# microBackpack.net
KiCad netlist of a schematic drawn in EAGLE
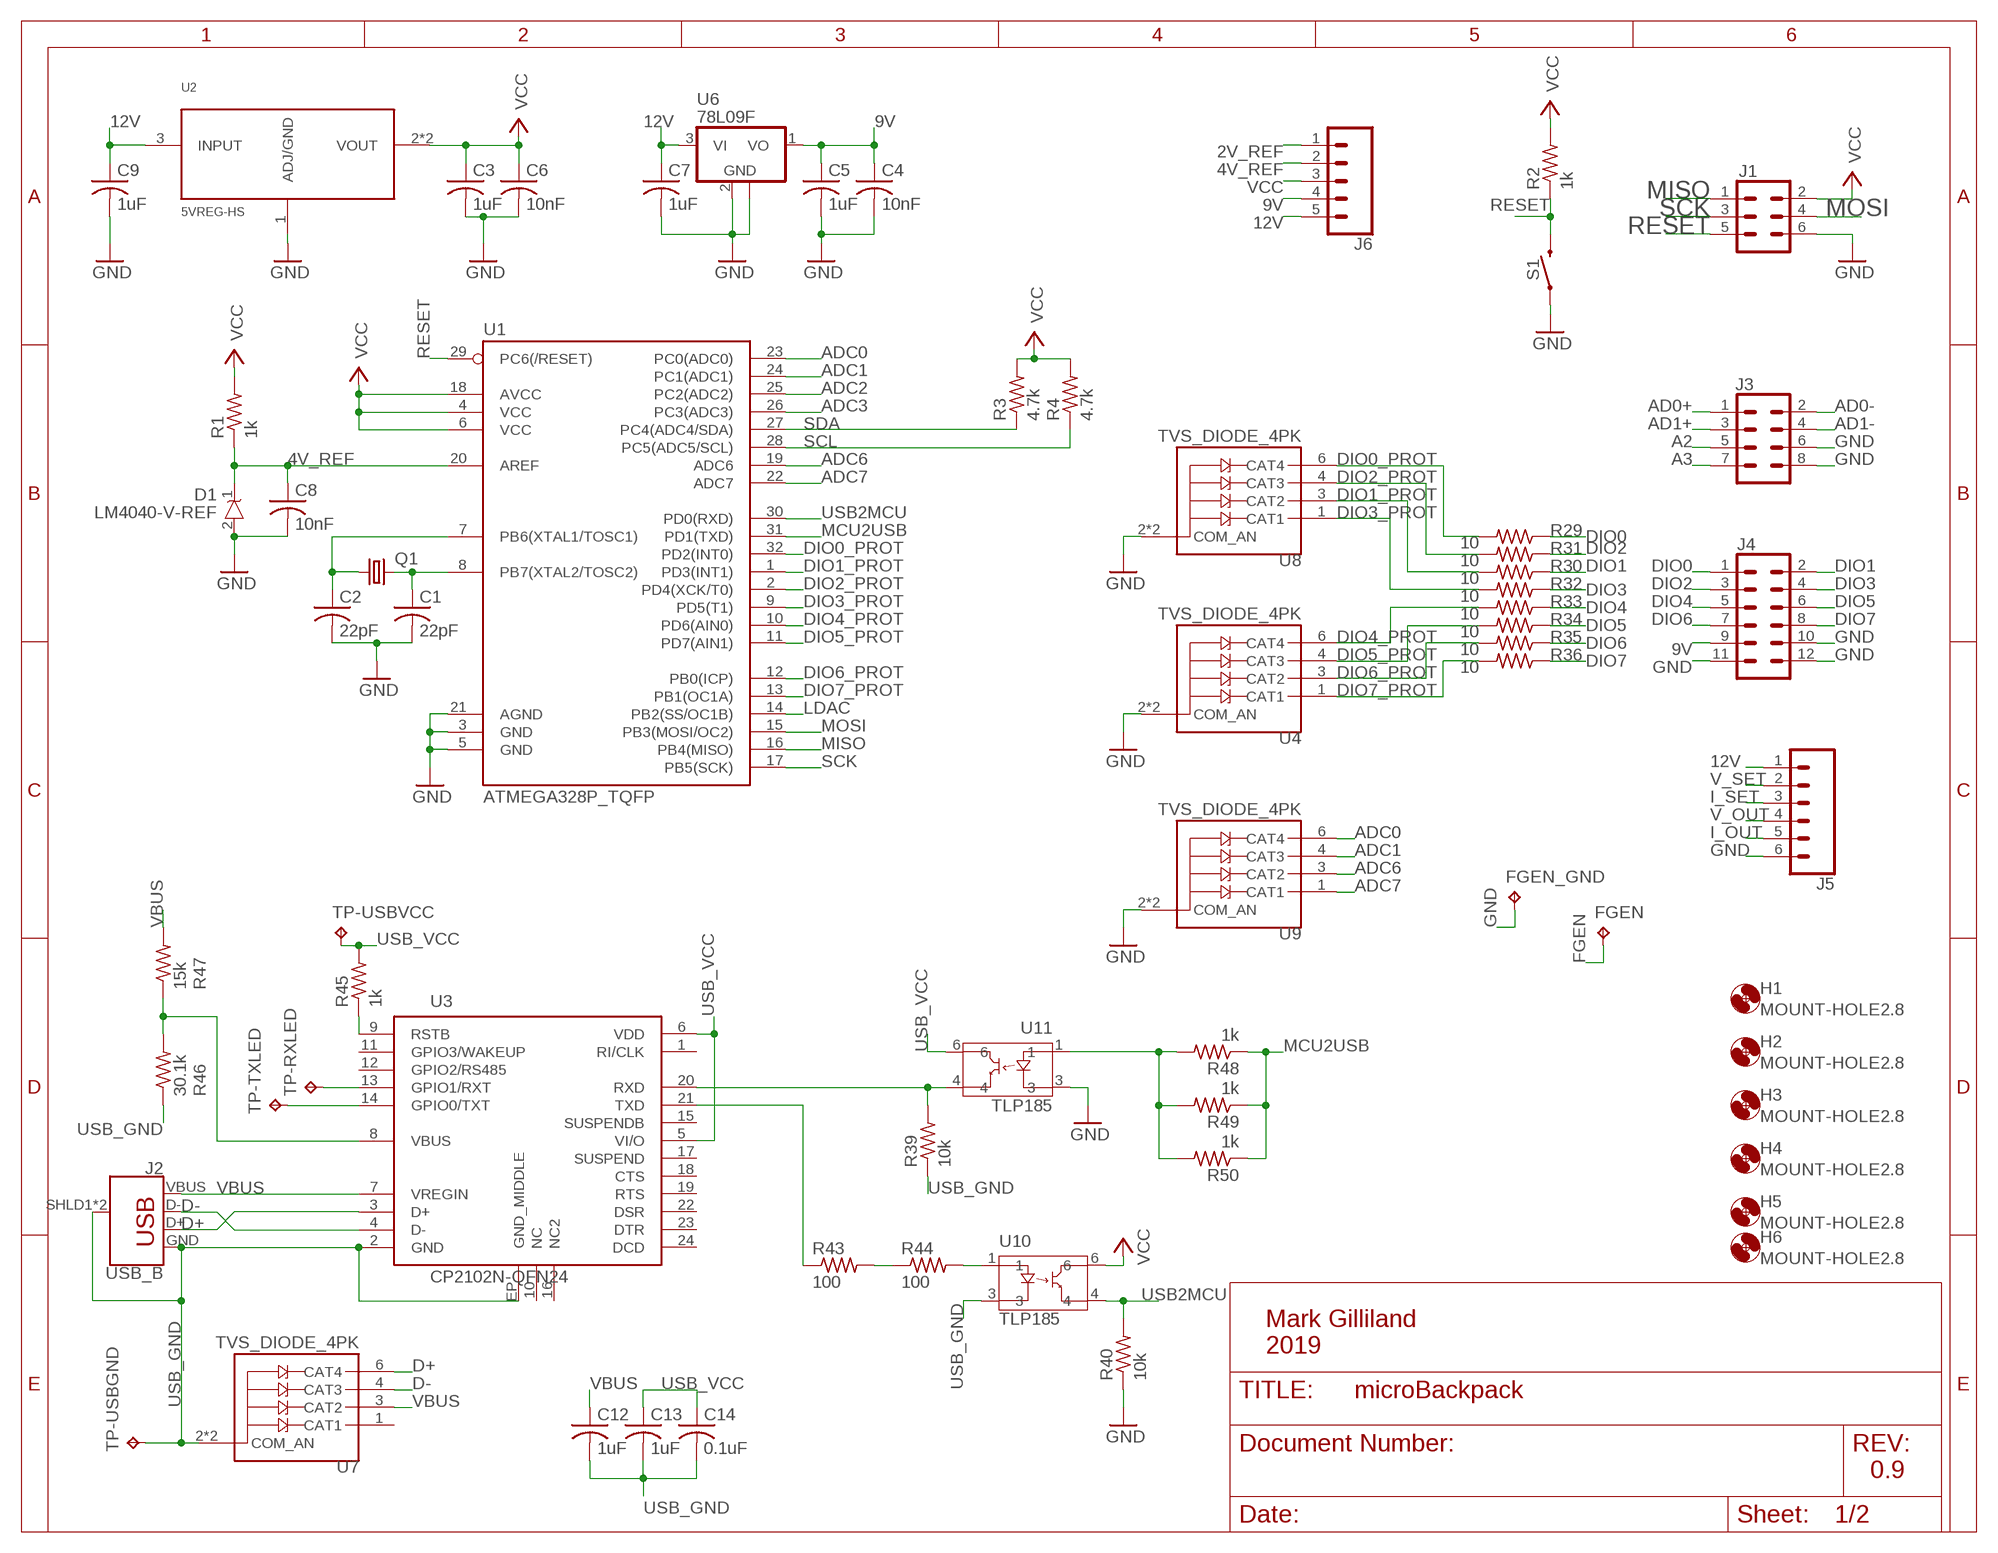
[diagram p0: schematic, sheet 1]
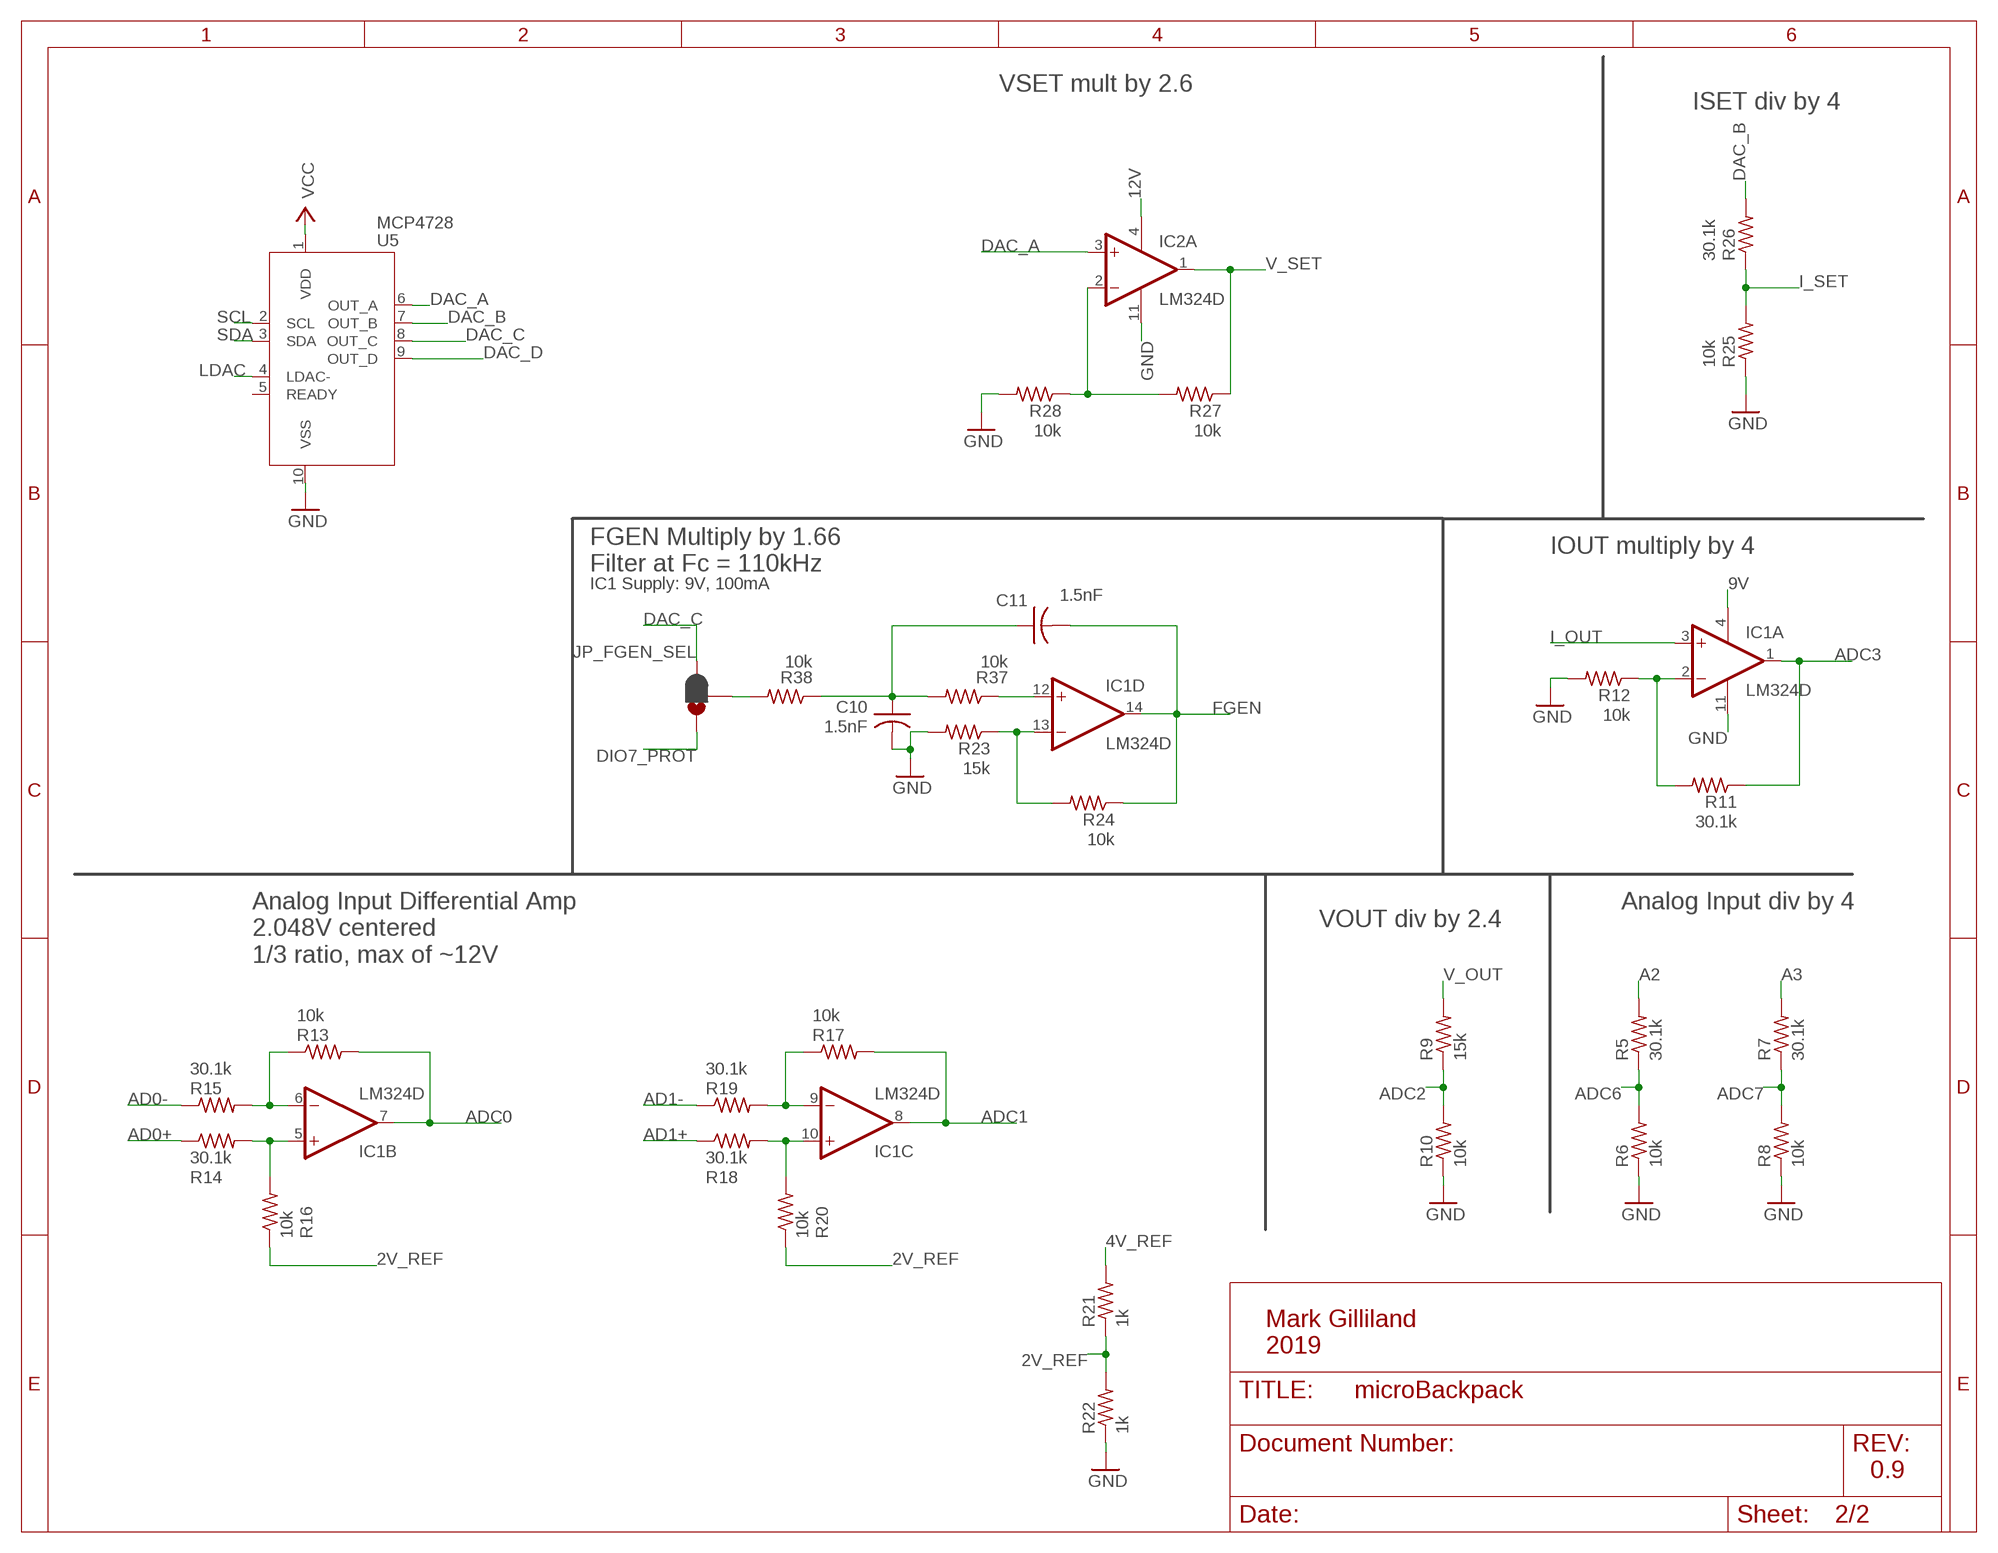
[diagram p1: schematic, sheet 2]

(export (version "E")
  (design (tool "Eeschema 10.0.6"))
  (components
    (comp (ref "C10")
      (value "1.5nF")
      (footprint "eagle-import:C0805")
      (libsource (lib "eagle-import") (part "C-USC0805"))
    )
    (comp (ref "C11")
      (value "1.5nF")
      (footprint "eagle-import:C0805")
      (libsource (lib "eagle-import") (part "C-USC0805"))
    )
    (comp (ref "IC1")
      (value "LM324D")
      (footprint "eagle-import:SO14")
      (libsource (lib "eagle-import") (part "LM324D"))
    )
    (comp (ref "IC2")
      (value "LM324D")
      (footprint "eagle-import:SO14")
      (libsource (lib "eagle-import") (part "LM324D"))
    )
    (comp (ref "JP_FGEN_SEL")
      (value "JUMPER-SMT_3_1-NC_PASTE_SILK")
      (footprint "eagle-import:SMT-JUMPER_3_1-NC_PASTE_SILK")
      (libsource (lib "eagle-import") (part "JUMPER-SMT_3_1-NC_PASTE_SILK"))
    )
    (comp (ref "R5")
      (value "30.1k")
      (footprint "eagle-import:R0805")
      (libsource (lib "eagle-import") (part "R-US_R0805"))
    )
    (comp (ref "R6")
      (value "10k")
      (footprint "eagle-import:R0805")
      (libsource (lib "eagle-import") (part "R-US_R0805"))
    )
    (comp (ref "R7")
      (value "30.1k")
      (footprint "eagle-import:R0805")
      (libsource (lib "eagle-import") (part "R-US_R0805"))
    )
    (comp (ref "R8")
      (value "10k")
      (footprint "eagle-import:R0805")
      (libsource (lib "eagle-import") (part "R-US_R0805"))
    )
    (comp (ref "R9")
      (value "15k")
      (footprint "eagle-import:R0805")
      (libsource (lib "eagle-import") (part "R-US_R0805"))
    )
    (comp (ref "R10")
      (value "10k")
      (footprint "eagle-import:R0805")
      (libsource (lib "eagle-import") (part "R-US_R0805"))
    )
    (comp (ref "R11")
      (value "30.1k")
      (footprint "eagle-import:R0805")
      (libsource (lib "eagle-import") (part "R-US_R0805"))
    )
    (comp (ref "R12")
      (value "10k")
      (footprint "eagle-import:R0805")
      (libsource (lib "eagle-import") (part "R-US_R0805"))
    )
    (comp (ref "R13")
      (value "10k")
      (footprint "eagle-import:R0805")
      (libsource (lib "eagle-import") (part "R-US_R0805"))
    )
    (comp (ref "R14")
      (value "30.1k")
      (footprint "eagle-import:R0805")
      (libsource (lib "eagle-import") (part "R-US_R0805"))
    )
    (comp (ref "R15")
      (value "30.1k")
      (footprint "eagle-import:R0805")
      (libsource (lib "eagle-import") (part "R-US_R0805"))
    )
    (comp (ref "R16")
      (value "10k")
      (footprint "eagle-import:R0805")
      (libsource (lib "eagle-import") (part "R-US_R0805"))
    )
    (comp (ref "R17")
      (value "10k")
      (footprint "eagle-import:R0805")
      (libsource (lib "eagle-import") (part "R-US_R0805"))
    )
    (comp (ref "R18")
      (value "30.1k")
      (footprint "eagle-import:R0805")
      (libsource (lib "eagle-import") (part "R-US_R0805"))
    )
    (comp (ref "R19")
      (value "30.1k")
      (footprint "eagle-import:R0805")
      (libsource (lib "eagle-import") (part "R-US_R0805"))
    )
    (comp (ref "R20")
      (value "10k")
      (footprint "eagle-import:R0805")
      (libsource (lib "eagle-import") (part "R-US_R0805"))
    )
    (comp (ref "R21")
      (value "1k")
      (footprint "eagle-import:R0805")
      (libsource (lib "eagle-import") (part "R-US_R0805"))
    )
    (comp (ref "R22")
      (value "1k")
      (footprint "eagle-import:R0805")
      (libsource (lib "eagle-import") (part "R-US_R0805"))
    )
    (comp (ref "R23")
      (value "15k")
      (footprint "eagle-import:R0805")
      (libsource (lib "eagle-import") (part "R-US_R0805"))
    )
    (comp (ref "R24")
      (value "10k")
      (footprint "eagle-import:R0805")
      (libsource (lib "eagle-import") (part "R-US_R0805"))
    )
    (comp (ref "R25")
      (value "10k")
      (footprint "eagle-import:R0805")
      (libsource (lib "eagle-import") (part "R-US_R0805"))
    )
    (comp (ref "R26")
      (value "30.1k")
      (footprint "eagle-import:R0805")
      (libsource (lib "eagle-import") (part "R-US_R0805"))
    )
    (comp (ref "R27")
      (value "10k")
      (footprint "eagle-import:R0805")
      (libsource (lib "eagle-import") (part "R-US_R0805"))
    )
    (comp (ref "R28")
      (value "10k")
      (footprint "eagle-import:R0805")
      (libsource (lib "eagle-import") (part "R-US_R0805"))
    )
    (comp (ref "R37")
      (value "10k")
      (footprint "eagle-import:R0805")
      (libsource (lib "eagle-import") (part "R-US_R0805"))
    )
    (comp (ref "R38")
      (value "10k")
      (footprint "eagle-import:R0805")
      (libsource (lib "eagle-import") (part "R-US_R0805"))
    )
    (comp (ref "U5")
      (value "MCP4728")
      (footprint "eagle-import:MSOP10")
      (libsource (lib "eagle-import") (part "MCP4728"))
    )
    (comp (ref "C1")
      (value "22pF")
      (footprint "eagle-import:C0805")
      (libsource (lib "eagle-import") (part "C-USC0805"))
    )
    (comp (ref "C2")
      (value "22pF")
      (footprint "eagle-import:C0805")
      (libsource (lib "eagle-import") (part "C-USC0805"))
    )
    (comp (ref "C3")
      (value "1uF")
      (footprint "eagle-import:C0805")
      (libsource (lib "eagle-import") (part "C-USC0805"))
    )
    (comp (ref "C4")
      (value "10nF")
      (footprint "eagle-import:C0805")
      (libsource (lib "eagle-import") (part "C-USC0805"))
    )
    (comp (ref "C5")
      (value "1uF")
      (footprint "eagle-import:C0805")
      (libsource (lib "eagle-import") (part "C-USC0805"))
    )
    (comp (ref "C6")
      (value "10nF")
      (footprint "eagle-import:C0805")
      (libsource (lib "eagle-import") (part "C-USC0805"))
    )
    (comp (ref "C7")
      (value "1uF")
      (footprint "eagle-import:C0805")
      (libsource (lib "eagle-import") (part "C-USC0805"))
    )
    (comp (ref "C8")
      (value "10nF")
      (footprint "eagle-import:C0805")
      (libsource (lib "eagle-import") (part "C-USC0805"))
    )
    (comp (ref "C9")
      (value "1uF")
      (footprint "eagle-import:C0805")
      (libsource (lib "eagle-import") (part "C-USC0805"))
    )
    (comp (ref "C12")
      (value "1uF")
      (footprint "eagle-import:C0805")
      (libsource (lib "eagle-import") (part "C-USC0805"))
    )
    (comp (ref "C13")
      (value "1uF")
      (footprint "eagle-import:C0805")
      (libsource (lib "eagle-import") (part "C-USC0805"))
    )
    (comp (ref "C14")
      (value "0.1uF")
      (footprint "eagle-import:C0805")
      (libsource (lib "eagle-import") (part "C-USC0805"))
    )
    (comp (ref "D1")
      (value "LM4040-V-REF")
      (footprint "eagle-import:SOT23")
      (libsource (lib "eagle-import") (part "LM4040-V-REF"))
    )
    (comp (ref "FGEN")
      (value "TPPAD1-20Y")
      (footprint "eagle-import:P1-20Y")
      (libsource (lib "eagle-import") (part "TPPAD1-20Y"))
    )
    (comp (ref "FGEN_GND")
      (value "TPPAD1-20Y")
      (footprint "eagle-import:P1-20Y")
      (libsource (lib "eagle-import") (part "TPPAD1-20Y"))
    )
    (comp (ref "H1")
      (value "MOUNT-HOLE2.8")
      (footprint "eagle-import:2,8")
      (libsource (lib "eagle-import") (part "MOUNT-HOLE2.8"))
    )
    (comp (ref "H2")
      (value "MOUNT-HOLE2.8")
      (footprint "eagle-import:2,8")
      (libsource (lib "eagle-import") (part "MOUNT-HOLE2.8"))
    )
    (comp (ref "H3")
      (value "MOUNT-HOLE2.8")
      (footprint "eagle-import:2,8")
      (libsource (lib "eagle-import") (part "MOUNT-HOLE2.8"))
    )
    (comp (ref "H4")
      (value "MOUNT-HOLE2.8")
      (footprint "eagle-import:2,8")
      (libsource (lib "eagle-import") (part "MOUNT-HOLE2.8"))
    )
    (comp (ref "H5")
      (value "MOUNT-HOLE2.8")
      (footprint "eagle-import:2,8")
      (libsource (lib "eagle-import") (part "MOUNT-HOLE2.8"))
    )
    (comp (ref "H6")
      (value "MOUNT-HOLE2.8")
      (footprint "eagle-import:2,8")
      (libsource (lib "eagle-import") (part "MOUNT-HOLE2.8"))
    )
    (comp (ref "J1")
      (value "CONN_03X22X3_SILK_MALE_PTH")
      (footprint "eagle-import:2X3")
      (libsource (lib "eagle-import") (part "CONN_03X22X3_SILK_MALE_PTH"))
    )
    (comp (ref "J2")
      (value "USB_B")
      (footprint "eagle-import:USB-B-PTH-VERT")
      (libsource (lib "eagle-import") (part "USB_B"))
    )
    (comp (ref "J3")
      (value "CONN_04X2")
      (footprint "eagle-import:2X4")
      (libsource (lib "eagle-import") (part "CONN_04X2"))
    )
    (comp (ref "J4")
      (value "2X6 FEMALE")
      (footprint "eagle-import:2X6")
      (libsource (lib "eagle-import") (part "CONN_06X2PTH_FEMALE"))
    )
    (comp (ref "J5")
      (value "CONN_06SILK_FEMALE_PTH")
      (footprint "eagle-import:1X06")
      (libsource (lib "eagle-import") (part "CONN_06SILK_FEMALE_PTH"))
    )
    (comp (ref "J6")
      (value "CONN_05NO_SILK")
      (footprint "eagle-import:1X05_NO_SILK")
      (libsource (lib "eagle-import") (part "CONN_05NO_SILK"))
    )
    (comp (ref "Q1")
      (value "CRYSTALHC49U70")
      (footprint "eagle-import:HC49U70")
      (libsource (lib "eagle-import") (part "CRYSTALHC49U70"))
    )
    (comp (ref "R1")
      (value "1k")
      (footprint "eagle-import:R0805")
      (libsource (lib "eagle-import") (part "R-US_R0805"))
    )
    (comp (ref "R2")
      (value "1k")
      (footprint "eagle-import:R0805")
      (libsource (lib "eagle-import") (part "R-US_R0805"))
    )
    (comp (ref "R3")
      (value "4.7k")
      (footprint "eagle-import:R0805")
      (libsource (lib "eagle-import") (part "R-US_R0805"))
    )
    (comp (ref "R4")
      (value "4.7k")
      (footprint "eagle-import:R0805")
      (libsource (lib "eagle-import") (part "R-US_R0805"))
    )
    (comp (ref "R29")
      (value "10")
      (footprint "eagle-import:R0805")
      (libsource (lib "eagle-import") (part "R-US_R0805"))
    )
    (comp (ref "R30")
      (value "10")
      (footprint "eagle-import:R0805")
      (libsource (lib "eagle-import") (part "R-US_R0805"))
    )
    (comp (ref "R31")
      (value "10")
      (footprint "eagle-import:R0805")
      (libsource (lib "eagle-import") (part "R-US_R0805"))
    )
    (comp (ref "R32")
      (value "10")
      (footprint "eagle-import:R0805")
      (libsource (lib "eagle-import") (part "R-US_R0805"))
    )
    (comp (ref "R33")
      (value "10")
      (footprint "eagle-import:R0805")
      (libsource (lib "eagle-import") (part "R-US_R0805"))
    )
    (comp (ref "R34")
      (value "10")
      (footprint "eagle-import:R0805")
      (libsource (lib "eagle-import") (part "R-US_R0805"))
    )
    (comp (ref "R35")
      (value "10")
      (footprint "eagle-import:R0805")
      (libsource (lib "eagle-import") (part "R-US_R0805"))
    )
    (comp (ref "R36")
      (value "10")
      (footprint "eagle-import:R0805")
      (libsource (lib "eagle-import") (part "R-US_R0805"))
    )
    (comp (ref "R39")
      (value "10k")
      (footprint "eagle-import:R0805")
      (libsource (lib "eagle-import") (part "R-US_R0805"))
    )
    (comp (ref "R40")
      (value "10k")
      (footprint "eagle-import:R0805")
      (libsource (lib "eagle-import") (part "R-US_R0805"))
    )
    (comp (ref "R43")
      (value "100")
      (footprint "eagle-import:R0603")
      (libsource (lib "eagle-import") (part "R-US_R0603"))
    )
    (comp (ref "R44")
      (value "100")
      (footprint "eagle-import:R0603")
      (libsource (lib "eagle-import") (part "R-US_R0603"))
    )
    (comp (ref "R45")
      (value "1k")
      (footprint "eagle-import:R0805")
      (libsource (lib "eagle-import") (part "R-US_R0805"))
    )
    (comp (ref "R46")
      (value "30.1k")
      (footprint "eagle-import:R0805")
      (libsource (lib "eagle-import") (part "R-US_R0805"))
    )
    (comp (ref "R47")
      (value "15k")
      (footprint "eagle-import:R0805")
      (libsource (lib "eagle-import") (part "R-US_R0805"))
    )
    (comp (ref "R48")
      (value "1k")
      (footprint "eagle-import:R0805")
      (libsource (lib "eagle-import") (part "R-US_R0805"))
    )
    (comp (ref "R49")
      (value "1k")
      (footprint "eagle-import:R0805")
      (libsource (lib "eagle-import") (part "R-US_R0805"))
    )
    (comp (ref "R50")
      (value "1k")
      (footprint "eagle-import:R0805")
      (libsource (lib "eagle-import") (part "R-US_R0805"))
    )
    (comp (ref "S1")
      (value "MOMENTARY-SWITCH-SPST-SMD-5.2-REDUNDANT")
      (footprint "eagle-import:TACTILE_SWITCH_SMD_5.2MM")
      (libsource (lib "eagle-import") (part "MOMENTARY-SWITCH-SPST-SMD-5.2-REDUNDANT"))
    )
    (comp (ref "TP-RXLED")
      (value "TPPAD1-13")
      (footprint "eagle-import:P1-13")
      (libsource (lib "eagle-import") (part "TPPAD1-13"))
    )
    (comp (ref "TP-TXLED")
      (value "TPPAD1-13")
      (footprint "eagle-import:P1-13")
      (libsource (lib "eagle-import") (part "TPPAD1-13"))
    )
    (comp (ref "TP-USBGND")
      (value "TPPAD1-13")
      (footprint "eagle-import:P1-13")
      (libsource (lib "eagle-import") (part "TPPAD1-13"))
    )
    (comp (ref "TP-USBVCC")
      (value "TPPAD1-13")
      (footprint "eagle-import:P1-13")
      (libsource (lib "eagle-import") (part "TPPAD1-13"))
    )
    (comp (ref "U1")
      (value "ATMEGA328P_TQFP")
      (footprint "eagle-import:TQFP32-08")
      (libsource (lib "eagle-import") (part "ATMEGA328P_TQFP"))
    )
    (comp (ref "U2")
      (value "5VREG-HS")
      (footprint "eagle-import:SOT223-HS")
      (libsource (lib "eagle-import") (part "5VREG-HS"))
    )
    (comp (ref "U3")
      (value "CP2102N-QFN24")
      (footprint "eagle-import:QFN-24_ALT2")
      (libsource (lib "eagle-import") (part "CP2102N-QFN24"))
    )
    (comp (ref "U4")
      (value "TVS_DIODE_4PK")
      (footprint "eagle-import:SOT457")
      (libsource (lib "eagle-import") (part "TVS_DIODE_4PK"))
    )
    (comp (ref "U6")
      (value "78L09F")
      (footprint "eagle-import:SOT89")
      (libsource (lib "eagle-import") (part "78LF09"))
    )
    (comp (ref "U7")
      (value "TVS_DIODE_4PK")
      (footprint "eagle-import:SOT457")
      (libsource (lib "eagle-import") (part "TVS_DIODE_4PK"))
    )
    (comp (ref "U8")
      (value "TVS_DIODE_4PK")
      (footprint "eagle-import:SOT457")
      (libsource (lib "eagle-import") (part "TVS_DIODE_4PK"))
    )
    (comp (ref "U9")
      (value "TVS_DIODE_4PK")
      (footprint "eagle-import:SOT457")
      (libsource (lib "eagle-import") (part "TVS_DIODE_4PK"))
    )
    (comp (ref "U10")
      (value "TLP185")
      (footprint "eagle-import:SO06-4")
      (libsource (lib "eagle-import") (part "TLP185"))
    )
    (comp (ref "U11")
      (value "TLP185")
      (footprint "eagle-import:SO06-4")
      (libsource (lib "eagle-import") (part "TLP185"))
    )
  )
  (nets
    (net (code "1") (name "2V_REF") (class "Default")
      (node (ref "J6") (pin "1") (pinfunction "1_1") (pintype "passive"))
      (node (ref "R16") (pin "1") (pinfunction "1_1") (pintype "passive"))
      (node (ref "R20") (pin "1") (pinfunction "1_1") (pintype "passive"))
      (node (ref "R21") (pin "1") (pinfunction "1_1") (pintype "passive"))
      (node (ref "R22") (pin "2") (pinfunction "2_2") (pintype "passive"))
    )
    (net (code "2") (name "4V_REF") (class "Default")
      (node (ref "C8") (pin "1") (pinfunction "1_1") (pintype "passive"))
      (node (ref "D1") (pin "1") (pinfunction "+IN_1") (pintype "bidirectional"))
      (node (ref "J6") (pin "2") (pinfunction "2_2") (pintype "passive"))
      (node (ref "R1") (pin "1") (pinfunction "1_1") (pintype "passive"))
      (node (ref "R21") (pin "2") (pinfunction "2_2") (pintype "passive"))
      (node (ref "U1") (pin "20") (pinfunction "AREF_20") (pintype "bidirectional"))
    )
    (net (code "3") (name "9V") (class "Default")
      (node (ref "C4") (pin "1") (pinfunction "1_1") (pintype "passive"))
      (node (ref "C5") (pin "1") (pinfunction "1_1") (pintype "passive"))
      (node (ref "IC1") (pin "4") (pinfunction "V+_4") (pintype "power_in"))
      (node (ref "J4") (pin "9") (pinfunction "9_9") (pintype "passive"))
      (node (ref "J6") (pin "4") (pinfunction "4_4") (pintype "passive"))
      (node (ref "U6") (pin "1") (pinfunction "VO_1") (pintype "passive"))
    )
    (net (code "4") (name "12V") (class "Default")
      (node (ref "C7") (pin "1") (pinfunction "1_1") (pintype "passive"))
      (node (ref "C9") (pin "1") (pinfunction "1_1") (pintype "passive"))
      (node (ref "IC2") (pin "4") (pinfunction "V+_4") (pintype "power_in"))
      (node (ref "J5") (pin "1") (pinfunction "1_1") (pintype "passive"))
      (node (ref "J6") (pin "5") (pinfunction "5_5") (pintype "passive"))
      (node (ref "U2") (pin "3") (pinfunction "INPUT_3") (pintype "bidirectional"))
      (node (ref "U6") (pin "3") (pinfunction "VI_3") (pintype "input"))
    )
    (net (code "5") (name "A2") (class "Default")
      (node (ref "J3") (pin "5") (pinfunction "5_5") (pintype "passive"))
      (node (ref "R5") (pin "2") (pinfunction "2_2") (pintype "passive"))
    )
    (net (code "6") (name "A3") (class "Default")
      (node (ref "J3") (pin "7") (pinfunction "7_7") (pintype "passive"))
      (node (ref "R7") (pin "2") (pinfunction "2_2") (pintype "passive"))
    )
    (net (code "7") (name "AD0+") (class "Default")
      (node (ref "J3") (pin "1") (pinfunction "1_1") (pintype "passive"))
      (node (ref "R14") (pin "1") (pinfunction "1_1") (pintype "passive"))
    )
    (net (code "8") (name "AD0-") (class "Default")
      (node (ref "J3") (pin "2") (pinfunction "2_2") (pintype "passive"))
      (node (ref "R15") (pin "1") (pinfunction "1_1") (pintype "passive"))
    )
    (net (code "9") (name "AD1+") (class "Default")
      (node (ref "J3") (pin "3") (pinfunction "3_3") (pintype "passive"))
      (node (ref "R18") (pin "1") (pinfunction "1_1") (pintype "passive"))
    )
    (net (code "10") (name "AD1-") (class "Default")
      (node (ref "J3") (pin "4") (pinfunction "4_4") (pintype "passive"))
      (node (ref "R19") (pin "1") (pinfunction "1_1") (pintype "passive"))
    )
    (net (code "11") (name "ADC0") (class "Default")
      (node (ref "IC1") (pin "7") (pinfunction "OUT_7") (pintype "output"))
      (node (ref "R13") (pin "2") (pinfunction "2_2") (pintype "passive"))
      (node (ref "U1") (pin "23") (pinfunction "PC0(ADC0)_23") (pintype "bidirectional"))
      (node (ref "U9") (pin "6") (pinfunction "CAT4_6") (pintype "bidirectional"))
    )
    (net (code "12") (name "ADC1") (class "Default")
      (node (ref "IC1") (pin "8") (pinfunction "OUT_8") (pintype "output"))
      (node (ref "R17") (pin "2") (pinfunction "2_2") (pintype "passive"))
      (node (ref "U1") (pin "24") (pinfunction "PC1(ADC1)_24") (pintype "bidirectional"))
      (node (ref "U9") (pin "4") (pinfunction "CAT3_4") (pintype "bidirectional"))
    )
    (net (code "13") (name "ADC2") (class "Default")
      (node (ref "R10") (pin "2") (pinfunction "2_2") (pintype "passive"))
      (node (ref "R9") (pin "1") (pinfunction "1_1") (pintype "passive"))
      (node (ref "U1") (pin "25") (pinfunction "PC2(ADC2)_25") (pintype "bidirectional"))
    )
    (net (code "14") (name "ADC3") (class "Default")
      (node (ref "IC1") (pin "1") (pinfunction "OUT_1") (pintype "output"))
      (node (ref "R11") (pin "1") (pinfunction "1_1") (pintype "passive"))
      (node (ref "U1") (pin "26") (pinfunction "PC3(ADC3)_26") (pintype "bidirectional"))
    )
    (net (code "15") (name "ADC6") (class "Default")
      (node (ref "R5") (pin "1") (pinfunction "1_1") (pintype "passive"))
      (node (ref "R6") (pin "2") (pinfunction "2_2") (pintype "passive"))
      (node (ref "U1") (pin "19") (pinfunction "ADC6_19") (pintype "bidirectional"))
      (node (ref "U9") (pin "3") (pinfunction "CAT2_3") (pintype "bidirectional"))
    )
    (net (code "16") (name "ADC7") (class "Default")
      (node (ref "R7") (pin "1") (pinfunction "1_1") (pintype "passive"))
      (node (ref "R8") (pin "2") (pinfunction "2_2") (pintype "passive"))
      (node (ref "U1") (pin "22") (pinfunction "ADC7_22") (pintype "bidirectional"))
      (node (ref "U9") (pin "1") (pinfunction "CAT1_1") (pintype "bidirectional"))
    )
    (net (code "17") (name "D+") (class "Default")
      (node (ref "J2") (pin "D+") (pinfunction "D+_D+") (pintype "bidirectional"))
      (node (ref "U3") (pin "3") (pinfunction "D+_3") (pintype "bidirectional"))
      (node (ref "U7") (pin "6") (pinfunction "CAT4_6") (pintype "bidirectional"))
    )
    (net (code "18") (name "D-") (class "Default")
      (node (ref "J2") (pin "D-") (pinfunction "D-_D-") (pintype "bidirectional"))
      (node (ref "U3") (pin "4") (pinfunction "D-_4") (pintype "bidirectional"))
      (node (ref "U7") (pin "4") (pinfunction "CAT3_4") (pintype "bidirectional"))
    )
    (net (code "19") (name "DAC_A") (class "Default")
      (node (ref "IC2") (pin "3") (pinfunction "+IN_3") (pintype "input"))
      (node (ref "U5") (pin "6") (pinfunction "OUT_A_6") (pintype "bidirectional"))
    )
    (net (code "20") (name "DAC_B") (class "Default")
      (node (ref "R26") (pin "2") (pinfunction "2_2") (pintype "passive"))
      (node (ref "U5") (pin "7") (pinfunction "OUT_B_7") (pintype "bidirectional"))
    )
    (net (code "21") (name "DAC_C") (class "Default")
      (node (ref "JP_FGEN_SEL") (pin "3") (pinfunction "3_3") (pintype "passive"))
      (node (ref "U5") (pin "8") (pinfunction "OUT_C_8") (pintype "bidirectional"))
    )
    (net (code "22") (name "DAC_D") (class "Default")
      (node (ref "U5") (pin "9") (pinfunction "OUT_D_9") (pintype "bidirectional"))
    )
    (net (code "23") (name "DIO0") (class "Default")
      (node (ref "J4") (pin "1") (pinfunction "1_1") (pintype "passive"))
      (node (ref "R29") (pin "1") (pinfunction "1_1") (pintype "passive"))
    )
    (net (code "24") (name "DIO0_PROT") (class "Default")
      (node (ref "R29") (pin "2") (pinfunction "2_2") (pintype "passive"))
      (node (ref "U1") (pin "32") (pinfunction "PD2(INT0)_32") (pintype "bidirectional"))
      (node (ref "U8") (pin "6") (pinfunction "CAT4_6") (pintype "bidirectional"))
    )
    (net (code "25") (name "DIO1") (class "Default")
      (node (ref "J4") (pin "2") (pinfunction "2_2") (pintype "passive"))
      (node (ref "R30") (pin "1") (pinfunction "1_1") (pintype "passive"))
    )
    (net (code "26") (name "DIO1_PROT") (class "Default")
      (node (ref "R30") (pin "2") (pinfunction "2_2") (pintype "passive"))
      (node (ref "U1") (pin "1") (pinfunction "PD3(INT1)_1") (pintype "bidirectional"))
      (node (ref "U8") (pin "3") (pinfunction "CAT2_3") (pintype "bidirectional"))
    )
    (net (code "27") (name "DIO2") (class "Default")
      (node (ref "J4") (pin "3") (pinfunction "3_3") (pintype "passive"))
      (node (ref "R31") (pin "1") (pinfunction "1_1") (pintype "passive"))
    )
    (net (code "28") (name "DIO2_PROT") (class "Default")
      (node (ref "R31") (pin "2") (pinfunction "2_2") (pintype "passive"))
      (node (ref "U1") (pin "2") (pinfunction "PD4(XCK/T0)_2") (pintype "bidirectional"))
      (node (ref "U8") (pin "4") (pinfunction "CAT3_4") (pintype "bidirectional"))
    )
    (net (code "29") (name "DIO3") (class "Default")
      (node (ref "J4") (pin "4") (pinfunction "4_4") (pintype "passive"))
      (node (ref "R32") (pin "1") (pinfunction "1_1") (pintype "passive"))
    )
    (net (code "30") (name "DIO3_PROT") (class "Default")
      (node (ref "R32") (pin "2") (pinfunction "2_2") (pintype "passive"))
      (node (ref "U1") (pin "9") (pinfunction "PD5(T1)_9") (pintype "bidirectional"))
      (node (ref "U8") (pin "1") (pinfunction "CAT1_1") (pintype "bidirectional"))
    )
    (net (code "31") (name "DIO4") (class "Default")
      (node (ref "J4") (pin "5") (pinfunction "5_5") (pintype "passive"))
      (node (ref "R33") (pin "1") (pinfunction "1_1") (pintype "passive"))
    )
    (net (code "32") (name "DIO4_PROT") (class "Default")
      (node (ref "R33") (pin "2") (pinfunction "2_2") (pintype "passive"))
      (node (ref "U1") (pin "10") (pinfunction "PD6(AIN0)_10") (pintype "bidirectional"))
      (node (ref "U4") (pin "6") (pinfunction "CAT4_6") (pintype "bidirectional"))
    )
    (net (code "33") (name "DIO5") (class "Default")
      (node (ref "J4") (pin "6") (pinfunction "6_6") (pintype "passive"))
      (node (ref "R34") (pin "1") (pinfunction "1_1") (pintype "passive"))
    )
    (net (code "34") (name "DIO5_PROT") (class "Default")
      (node (ref "R34") (pin "2") (pinfunction "2_2") (pintype "passive"))
      (node (ref "U1") (pin "11") (pinfunction "PD7(AIN1)_11") (pintype "bidirectional"))
      (node (ref "U4") (pin "4") (pinfunction "CAT3_4") (pintype "bidirectional"))
    )
    (net (code "35") (name "DIO6") (class "Default")
      (node (ref "J4") (pin "7") (pinfunction "7_7") (pintype "passive"))
      (node (ref "R35") (pin "1") (pinfunction "1_1") (pintype "passive"))
    )
    (net (code "36") (name "DIO6_PROT") (class "Default")
      (node (ref "R35") (pin "2") (pinfunction "2_2") (pintype "passive"))
      (node (ref "U1") (pin "12") (pinfunction "PB0(ICP)_12") (pintype "bidirectional"))
      (node (ref "U4") (pin "3") (pinfunction "CAT2_3") (pintype "bidirectional"))
    )
    (net (code "37") (name "DIO7") (class "Default")
      (node (ref "J4") (pin "8") (pinfunction "8_8") (pintype "passive"))
      (node (ref "R36") (pin "1") (pinfunction "1_1") (pintype "passive"))
    )
    (net (code "38") (name "DIO7_PROT") (class "Default")
      (node (ref "JP_FGEN_SEL") (pin "1") (pinfunction "1_1") (pintype "passive"))
      (node (ref "R36") (pin "2") (pinfunction "2_2") (pintype "passive"))
      (node (ref "U1") (pin "13") (pinfunction "PB1(OC1A)_13") (pintype "bidirectional"))
      (node (ref "U4") (pin "1") (pinfunction "CAT1_1") (pintype "bidirectional"))
    )
    (net (code "39") (name "FGEN") (class "Default")
      (node (ref "C11") (pin "2") (pinfunction "2_2") (pintype "passive"))
      (node (ref "FGEN") (pin "TP") (pinfunction "TP_TP") (pintype "input"))
      (node (ref "IC1") (pin "14") (pinfunction "OUT_14") (pintype "output"))
      (node (ref "R24") (pin "1") (pinfunction "1_1") (pintype "passive"))
    )
    (net (code "40") (name "GND") (class "Default")
      (node (ref "C1") (pin "2") (pinfunction "2_2") (pintype "passive"))
      (node (ref "C10") (pin "2") (pinfunction "2_2") (pintype "passive"))
      (node (ref "C2") (pin "2") (pinfunction "2_2") (pintype "passive"))
      (node (ref "C3") (pin "2") (pinfunction "2_2") (pintype "passive"))
      (node (ref "C4") (pin "2") (pinfunction "2_2") (pintype "passive"))
      (node (ref "C5") (pin "2") (pinfunction "2_2") (pintype "passive"))
      (node (ref "C6") (pin "2") (pinfunction "2_2") (pintype "passive"))
      (node (ref "C7") (pin "2") (pinfunction "2_2") (pintype "passive"))
      (node (ref "C8") (pin "2") (pinfunction "2_2") (pintype "passive"))
      (node (ref "C9") (pin "2") (pinfunction "2_2") (pintype "passive"))
      (node (ref "D1") (pin "2") (pinfunction "-IN_2") (pintype "bidirectional"))
      (node (ref "FGEN_GND") (pin "TP") (pinfunction "TP_TP") (pintype "input"))
      (node (ref "IC1") (pin "11") (pinfunction "V-_11") (pintype "power_in"))
      (node (ref "IC2") (pin "11") (pinfunction "V-_11") (pintype "power_in"))
      (node (ref "J1") (pin "6") (pinfunction "6_6") (pintype "bidirectional"))
      (node (ref "J3") (pin "6") (pinfunction "6_6") (pintype "passive"))
      (node (ref "J3") (pin "8") (pinfunction "8_8") (pintype "passive"))
      (node (ref "J4") (pin "10") (pinfunction "10_10") (pintype "passive"))
      (node (ref "J4") (pin "11") (pinfunction "11_11") (pintype "passive"))
      (node (ref "J4") (pin "12") (pinfunction "12_12") (pintype "passive"))
      (node (ref "J5") (pin "6") (pinfunction "6_6") (pintype "passive"))
      (node (ref "R10") (pin "1") (pinfunction "1_1") (pintype "passive"))
      (node (ref "R12") (pin "2") (pinfunction "2_2") (pintype "passive"))
      (node (ref "R22") (pin "1") (pinfunction "1_1") (pintype "passive"))
      (node (ref "R23") (pin "2") (pinfunction "2_2") (pintype "passive"))
      (node (ref "R25") (pin "1") (pinfunction "1_1") (pintype "passive"))
      (node (ref "R28") (pin "2") (pinfunction "2_2") (pintype "passive"))
      (node (ref "R40") (pin "1") (pinfunction "1_1") (pintype "passive"))
      (node (ref "R6") (pin "1") (pinfunction "1_1") (pintype "passive"))
      (node (ref "R8") (pin "1") (pinfunction "1_1") (pintype "passive"))
      (node (ref "S1") (pin "1") (pinfunction "1_1") (pintype "passive"))
      (node (ref "S1") (pin "2") (pinfunction "1_2") (pintype "passive"))
      (node (ref "U1") (pin "21") (pinfunction "AGND_21") (pintype "bidirectional"))
      (node (ref "U1") (pin "3") (pinfunction "GND_3") (pintype "bidirectional"))
      (node (ref "U1") (pin "5") (pinfunction "GND_5") (pintype "bidirectional"))
      (node (ref "U11") (pin "3") (pinfunction "3_3") (pintype "bidirectional"))
      (node (ref "U2") (pin "1") (pinfunction "ADJ/GND_1") (pintype "bidirectional"))
      (node (ref "U4") (pin "2") (pinfunction "COM_AN_2") (pintype "bidirectional"))
      (node (ref "U4") (pin "5") (pinfunction "COM_AN_5") (pintype "bidirectional"))
      (node (ref "U5") (pin "10") (pinfunction "VSS_10") (pintype "bidirectional"))
      (node (ref "U6") (pin "2") (pinfunction "GND_2") (pintype "passive"))
      (node (ref "U6") (pin "2@1") (pinfunction "GND_2@1") (pintype "passive"))
      (node (ref "U8") (pin "2") (pinfunction "COM_AN_2") (pintype "bidirectional"))
      (node (ref "U8") (pin "5") (pinfunction "COM_AN_5") (pintype "bidirectional"))
      (node (ref "U9") (pin "2") (pinfunction "COM_AN_2") (pintype "bidirectional"))
      (node (ref "U9") (pin "5") (pinfunction "COM_AN_5") (pintype "bidirectional"))
    )
    (net (code "41") (name "I_OUT") (class "Default")
      (node (ref "IC1") (pin "3") (pinfunction "+IN_3") (pintype "input"))
      (node (ref "J5") (pin "5") (pinfunction "5_5") (pintype "passive"))
    )
    (net (code "42") (name "I_SET") (class "Default")
      (node (ref "J5") (pin "3") (pinfunction "3_3") (pintype "passive"))
      (node (ref "R25") (pin "2") (pinfunction "2_2") (pintype "passive"))
      (node (ref "R26") (pin "1") (pinfunction "1_1") (pintype "passive"))
    )
    (net (code "43") (name "LDAC") (class "Default")
      (node (ref "U1") (pin "14") (pinfunction "PB2(SS/OC1B)_14") (pintype "bidirectional"))
      (node (ref "U5") (pin "4") (pinfunction "LDAC-_4") (pintype "bidirectional"))
    )
    (net (code "44") (name "MCU2USB") (class "Default")
      (node (ref "R48") (pin "1") (pinfunction "1_1") (pintype "passive"))
      (node (ref "R49") (pin "1") (pinfunction "1_1") (pintype "passive"))
      (node (ref "R50") (pin "1") (pinfunction "1_1") (pintype "passive"))
      (node (ref "U1") (pin "31") (pinfunction "PD1(TXD)_31") (pintype "bidirectional"))
    )
    (net (code "45") (name "MISO") (class "Default")
      (node (ref "J1") (pin "1") (pinfunction "1_1") (pintype "bidirectional"))
      (node (ref "U1") (pin "16") (pinfunction "PB4(MISO)_16") (pintype "bidirectional"))
    )
    (net (code "46") (name "MOSI") (class "Default")
      (node (ref "J1") (pin "4") (pinfunction "4_4") (pintype "bidirectional"))
      (node (ref "U1") (pin "15") (pinfunction "PB3(MOSI/OC2)_15") (pintype "bidirectional"))
    )
    (net (code "47") (name "Net-(C10-Pad1)") (class "Default")
      (node (ref "C10") (pin "1") (pinfunction "1_1") (pintype "passive"))
      (node (ref "C11") (pin "1") (pinfunction "1_1") (pintype "passive"))
      (node (ref "R37") (pin "2") (pinfunction "2_2") (pintype "passive"))
      (node (ref "R38") (pin "1") (pinfunction "1_1") (pintype "passive"))
    )
    (net (code "48") (name "Net-(IC1A--IN)") (class "Default")
      (node (ref "IC1") (pin "2") (pinfunction "-IN_2") (pintype "input"))
      (node (ref "R11") (pin "2") (pinfunction "2_2") (pintype "passive"))
      (node (ref "R12") (pin "1") (pinfunction "1_1") (pintype "passive"))
    )
    (net (code "49") (name "Net-(IC1B-+IN)") (class "Default")
      (node (ref "IC1") (pin "5") (pinfunction "+IN_5") (pintype "input"))
      (node (ref "R14") (pin "2") (pinfunction "2_2") (pintype "passive"))
      (node (ref "R16") (pin "2") (pinfunction "2_2") (pintype "passive"))
    )
    (net (code "50") (name "Net-(IC1B--IN)") (class "Default")
      (node (ref "IC1") (pin "6") (pinfunction "-IN_6") (pintype "input"))
      (node (ref "R13") (pin "1") (pinfunction "1_1") (pintype "passive"))
      (node (ref "R15") (pin "2") (pinfunction "2_2") (pintype "passive"))
    )
    (net (code "51") (name "Net-(IC1C-+IN)") (class "Default")
      (node (ref "IC1") (pin "10") (pinfunction "+IN_10") (pintype "input"))
      (node (ref "R18") (pin "2") (pinfunction "2_2") (pintype "passive"))
      (node (ref "R20") (pin "2") (pinfunction "2_2") (pintype "passive"))
    )
    (net (code "52") (name "Net-(IC1C--IN)") (class "Default")
      (node (ref "IC1") (pin "9") (pinfunction "-IN_9") (pintype "input"))
      (node (ref "R17") (pin "1") (pinfunction "1_1") (pintype "passive"))
      (node (ref "R19") (pin "2") (pinfunction "2_2") (pintype "passive"))
    )
    (net (code "53") (name "Net-(IC1D-+IN)") (class "Default")
      (node (ref "IC1") (pin "12") (pinfunction "+IN_12") (pintype "input"))
      (node (ref "R37") (pin "1") (pinfunction "1_1") (pintype "passive"))
    )
    (net (code "54") (name "Net-(IC1D--IN)") (class "Default")
      (node (ref "IC1") (pin "13") (pinfunction "-IN_13") (pintype "input"))
      (node (ref "R23") (pin "1") (pinfunction "1_1") (pintype "passive"))
      (node (ref "R24") (pin "2") (pinfunction "2_2") (pintype "passive"))
    )
    (net (code "55") (name "Net-(IC2A--IN)") (class "Default")
      (node (ref "IC2") (pin "2") (pinfunction "-IN_2") (pintype "input"))
      (node (ref "R27") (pin "2") (pinfunction "2_2") (pintype "passive"))
      (node (ref "R28") (pin "1") (pinfunction "1_1") (pintype "passive"))
    )
    (net (code "56") (name "Net-(JP_FGEN_SEL-Pad2)") (class "Default")
      (node (ref "JP_FGEN_SEL") (pin "2") (pinfunction "2_2") (pintype "passive"))
      (node (ref "R38") (pin "2") (pinfunction "2_2") (pintype "passive"))
    )
    (net (code "57") (name "Net-(R43-Pad2)") (class "Default")
      (node (ref "R43") (pin "2") (pinfunction "2_2") (pintype "passive"))
      (node (ref "R44") (pin "1") (pinfunction "1_1") (pintype "passive"))
    )
    (net (code "58") (name "Net-(R44-Pad2)") (class "Default")
      (node (ref "R44") (pin "2") (pinfunction "2_2") (pintype "passive"))
      (node (ref "U10") (pin "1") (pinfunction "1_1") (pintype "bidirectional"))
    )
    (net (code "59") (name "Net-(R48-Pad2)") (class "Default")
      (node (ref "R48") (pin "2") (pinfunction "2_2") (pintype "passive"))
      (node (ref "R49") (pin "2") (pinfunction "2_2") (pintype "passive"))
      (node (ref "R50") (pin "2") (pinfunction "2_2") (pintype "passive"))
      (node (ref "U11") (pin "1") (pinfunction "1_1") (pintype "bidirectional"))
    )
    (net (code "60") (name "Net-(U1-PB6(XTAL1{slash}TOSC1))") (class "Default")
      (node (ref "C2") (pin "1") (pinfunction "1_1") (pintype "passive"))
      (node (ref "Q1") (pin "1") (pinfunction "1_1") (pintype "passive"))
      (node (ref "U1") (pin "7") (pinfunction "PB6(XTAL1/TOSC1)_7") (pintype "bidirectional"))
    )
    (net (code "61") (name "Net-(U1-PB7(XTAL2{slash}TOSC2))") (class "Default")
      (node (ref "C1") (pin "1") (pinfunction "1_1") (pintype "passive"))
      (node (ref "Q1") (pin "2") (pinfunction "2_2") (pintype "passive"))
      (node (ref "U1") (pin "8") (pinfunction "PB7(XTAL2/TOSC2)_8") (pintype "bidirectional"))
    )
    (net (code "62") (name "Net-(U3-GPIO0{slash}TXT)") (class "Default")
      (node (ref "TP-TXLED") (pin "TP") (pinfunction "TP_TP") (pintype "input"))
      (node (ref "U3") (pin "14") (pinfunction "GPIO0/TXT_14") (pintype "bidirectional"))
    )
    (net (code "63") (name "Net-(U3-GPIO1{slash}RXT)") (class "Default")
      (node (ref "TP-RXLED") (pin "TP") (pinfunction "TP_TP") (pintype "input"))
      (node (ref "U3") (pin "13") (pinfunction "GPIO1/RXT_13") (pintype "bidirectional"))
    )
    (net (code "64") (name "Net-(U3-RSTB)") (class "Default")
      (node (ref "R45") (pin "1") (pinfunction "1_1") (pintype "passive"))
      (node (ref "U3") (pin "9") (pinfunction "RSTB_9") (pintype "bidirectional"))
    )
    (net (code "65") (name "Net-(U3-RXD)") (class "Default")
      (node (ref "R39") (pin "2") (pinfunction "2_2") (pintype "passive"))
      (node (ref "U11") (pin "4") (pinfunction "4_4") (pintype "bidirectional"))
      (node (ref "U3") (pin "20") (pinfunction "RXD_20") (pintype "bidirectional"))
    )
    (net (code "66") (name "Net-(U3-TXD)") (class "Default")
      (node (ref "R43") (pin "1") (pinfunction "1_1") (pintype "passive"))
      (node (ref "U3") (pin "21") (pinfunction "TXD_21") (pintype "bidirectional"))
    )
    (net (code "67") (name "Net-(U3-VBUS)") (class "Default")
      (node (ref "R46") (pin "2") (pinfunction "2_2") (pintype "passive"))
      (node (ref "R47") (pin "1") (pinfunction "1_1") (pintype "passive"))
      (node (ref "U3") (pin "8") (pinfunction "VBUS_8") (pintype "bidirectional"))
    )
    (net (code "68") (name "RESET") (class "Default")
      (node (ref "J1") (pin "5") (pinfunction "5_5") (pintype "bidirectional"))
      (node (ref "R2") (pin "1") (pinfunction "1_1") (pintype "passive"))
      (node (ref "S1") (pin "3") (pinfunction "2_3") (pintype "passive"))
      (node (ref "S1") (pin "4") (pinfunction "2_4") (pintype "passive"))
      (node (ref "U1") (pin "29") (pinfunction "PC6(/RESET)_29") (pintype "bidirectional"))
    )
    (net (code "69") (name "SCK") (class "Default")
      (node (ref "J1") (pin "3") (pinfunction "3_3") (pintype "bidirectional"))
      (node (ref "U1") (pin "17") (pinfunction "PB5(SCK)_17") (pintype "bidirectional"))
    )
    (net (code "70") (name "SCL") (class "Default")
      (node (ref "R4") (pin "1") (pinfunction "1_1") (pintype "passive"))
      (node (ref "U1") (pin "28") (pinfunction "PC5(ADC5/SCL)_28") (pintype "bidirectional"))
      (node (ref "U5") (pin "2") (pinfunction "SCL_2") (pintype "bidirectional"))
    )
    (net (code "71") (name "SDA") (class "Default")
      (node (ref "R3") (pin "1") (pinfunction "1_1") (pintype "passive"))
      (node (ref "U1") (pin "27") (pinfunction "PC4(ADC4/SDA)_27") (pintype "bidirectional"))
      (node (ref "U5") (pin "3") (pinfunction "SDA_3") (pintype "bidirectional"))
    )
    (net (code "72") (name "USB2MCU") (class "Default")
      (node (ref "R40") (pin "2") (pinfunction "2_2") (pintype "passive"))
      (node (ref "U1") (pin "30") (pinfunction "PD0(RXD)_30") (pintype "bidirectional"))
      (node (ref "U10") (pin "4") (pinfunction "4_4") (pintype "bidirectional"))
    )
    (net (code "73") (name "USB_GND") (class "Default")
      (node (ref "C12") (pin "2") (pinfunction "2_2") (pintype "passive"))
      (node (ref "C13") (pin "2") (pinfunction "2_2") (pintype "passive"))
      (node (ref "C14") (pin "2") (pinfunction "2_2") (pintype "passive"))
      (node (ref "J2") (pin "GND") (pinfunction "GND_GND") (pintype "power_in"))
      (node (ref "J2") (pin "SHLD1") (pinfunction "SHIELD_SHLD1") (pintype "bidirectional"))
      (node (ref "J2") (pin "SHLD2") (pinfunction "SHIELD_SHLD2") (pintype "bidirectional"))
      (node (ref "R39") (pin "1") (pinfunction "1_1") (pintype "passive"))
      (node (ref "R46") (pin "1") (pinfunction "1_1") (pintype "passive"))
      (node (ref "TP-USBGND") (pin "TP") (pinfunction "TP_TP") (pintype "input"))
      (node (ref "U10") (pin "3") (pinfunction "3_3") (pintype "bidirectional"))
      (node (ref "U3") (pin "2") (pinfunction "GND_2") (pintype "bidirectional"))
      (node (ref "U3") (pin "EP") (pinfunction "GND_MIDDLE_EP") (pintype "bidirectional"))
      (node (ref "U7") (pin "2") (pinfunction "COM_AN_2") (pintype "bidirectional"))
      (node (ref "U7") (pin "5") (pinfunction "COM_AN_5") (pintype "bidirectional"))
    )
    (net (code "74") (name "USB_VCC") (class "Default")
      (node (ref "C13") (pin "1") (pinfunction "1_1") (pintype "passive"))
      (node (ref "C14") (pin "1") (pinfunction "1_1") (pintype "passive"))
      (node (ref "R45") (pin "2") (pinfunction "2_2") (pintype "passive"))
      (node (ref "TP-USBVCC") (pin "TP") (pinfunction "TP_TP") (pintype "input"))
      (node (ref "U11") (pin "6") (pinfunction "6_6") (pintype "bidirectional"))
      (node (ref "U3") (pin "5") (pinfunction "VI/O_5") (pintype "bidirectional"))
      (node (ref "U3") (pin "6") (pinfunction "VDD_6") (pintype "bidirectional"))
    )
    (net (code "75") (name "VBUS") (class "Default")
      (node (ref "C12") (pin "1") (pinfunction "1_1") (pintype "passive"))
      (node (ref "J2") (pin "VBUS") (pinfunction "VBUS_VBUS") (pintype "power_in"))
      (node (ref "R47") (pin "2") (pinfunction "2_2") (pintype "passive"))
      (node (ref "U3") (pin "7") (pinfunction "VREGIN_7") (pintype "bidirectional"))
      (node (ref "U7") (pin "3") (pinfunction "CAT2_3") (pintype "bidirectional"))
    )
    (net (code "76") (name "VCC") (class "Default")
      (node (ref "C3") (pin "1") (pinfunction "1_1") (pintype "passive"))
      (node (ref "C6") (pin "1") (pinfunction "1_1") (pintype "passive"))
      (node (ref "J1") (pin "2") (pinfunction "2_2") (pintype "bidirectional"))
      (node (ref "J6") (pin "3") (pinfunction "3_3") (pintype "passive"))
      (node (ref "R1") (pin "2") (pinfunction "2_2") (pintype "passive"))
      (node (ref "R2") (pin "2") (pinfunction "2_2") (pintype "passive"))
      (node (ref "R3") (pin "2") (pinfunction "2_2") (pintype "passive"))
      (node (ref "R4") (pin "2") (pinfunction "2_2") (pintype "passive"))
      (node (ref "U1") (pin "18") (pinfunction "AVCC_18") (pintype "bidirectional"))
      (node (ref "U1") (pin "4") (pinfunction "VCC_4") (pintype "bidirectional"))
      (node (ref "U1") (pin "6") (pinfunction "VCC_6") (pintype "bidirectional"))
      (node (ref "U10") (pin "6") (pinfunction "6_6") (pintype "bidirectional"))
      (node (ref "U2") (pin "2") (pinfunction "VOUT_2") (pintype "bidirectional"))
      (node (ref "U2") (pin "4") (pinfunction "VOUT_4") (pintype "bidirectional"))
      (node (ref "U5") (pin "1") (pinfunction "VDD_1") (pintype "bidirectional"))
    )
    (net (code "77") (name "V_OUT") (class "Default")
      (node (ref "J5") (pin "4") (pinfunction "4_4") (pintype "passive"))
      (node (ref "R9") (pin "2") (pinfunction "2_2") (pintype "passive"))
    )
    (net (code "78") (name "V_SET") (class "Default")
      (node (ref "IC2") (pin "1") (pinfunction "OUT_1") (pintype "output"))
      (node (ref "J5") (pin "2") (pinfunction "2_2") (pintype "passive"))
      (node (ref "R27") (pin "1") (pinfunction "1_1") (pintype "passive"))
    )
    (net (code "79") (name "unconnected-(U3-CTS-Pad18)") (class "Default")
      (node (ref "U3") (pin "18") (pinfunction "CTS_18") (pintype "bidirectional"))
    )
    (net (code "80") (name "unconnected-(U3-DCD-Pad24)") (class "Default")
      (node (ref "U3") (pin "24") (pinfunction "DCD_24") (pintype "bidirectional"))
    )
    (net (code "81") (name "unconnected-(U3-DSR-Pad22)") (class "Default")
      (node (ref "U3") (pin "22") (pinfunction "DSR_22") (pintype "bidirectional"))
    )
    (net (code "82") (name "unconnected-(U3-DTR-Pad23)") (class "Default")
      (node (ref "U3") (pin "23") (pinfunction "DTR_23") (pintype "bidirectional"))
    )
    (net (code "83") (name "unconnected-(U3-GPIO2{slash}RS485-Pad12)") (class "Default")
      (node (ref "U3") (pin "12") (pinfunction "GPIO2/RS485_12") (pintype "bidirectional"))
    )
    (net (code "84") (name "unconnected-(U3-GPIO3{slash}WAKEUP-Pad11)") (class "Default")
      (node (ref "U3") (pin "11") (pinfunction "GPIO3/WAKEUP_11") (pintype "bidirectional"))
    )
    (net (code "85") (name "unconnected-(U3-NC-Pad10)") (class "Default")
      (node (ref "U3") (pin "10") (pinfunction "NC_10") (pintype "bidirectional"))
    )
    (net (code "86") (name "unconnected-(U3-NC2-Pad16)") (class "Default")
      (node (ref "U3") (pin "16") (pinfunction "NC2_16") (pintype "bidirectional"))
    )
    (net (code "87") (name "unconnected-(U3-RI{slash}CLK-Pad1)") (class "Default")
      (node (ref "U3") (pin "1") (pinfunction "RI/CLK_1") (pintype "bidirectional"))
    )
    (net (code "88") (name "unconnected-(U3-RTS-Pad19)") (class "Default")
      (node (ref "U3") (pin "19") (pinfunction "RTS_19") (pintype "bidirectional"))
    )
    (net (code "89") (name "unconnected-(U3-SUSPEND-Pad17)") (class "Default")
      (node (ref "U3") (pin "17") (pinfunction "SUSPEND_17") (pintype "bidirectional"))
    )
    (net (code "90") (name "unconnected-(U3-SUSPENDB-Pad15)") (class "Default")
      (node (ref "U3") (pin "15") (pinfunction "SUSPENDB_15") (pintype "bidirectional"))
    )
    (net (code "91") (name "unconnected-(U5-READY-Pad5)") (class "Default")
      (node (ref "U5") (pin "5") (pinfunction "READY_5") (pintype "bidirectional"))
    )
    (net (code "92") (name "unconnected-(U7-CAT1-Pad1)") (class "Default")
      (node (ref "U7") (pin "1") (pinfunction "CAT1_1") (pintype "bidirectional"))
    )
  )
)
